# Sheet.net
KiCad netlist of a schematic drawn in Altium Designer
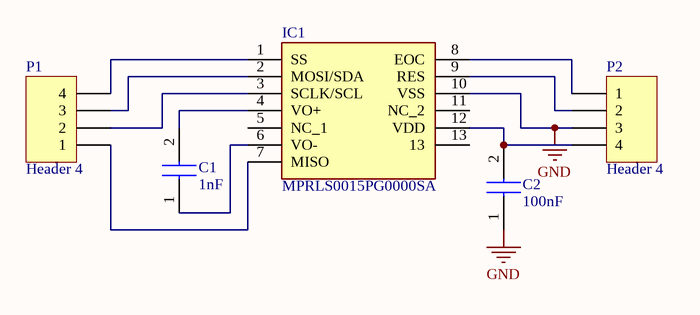
[diagram p0: Sheet.SchDoc]

(export (version "E")
  (design (tool "Eeschema 10.0.6"))
  (components
    (comp (ref "C1")
      (value "1nF")
      (footprint "SamacSys:CAPC2012X94N")
      (description "Capacitor")
      (fields
        (field (name "MANUFACTURER_PART_NUMBER") "08055A130JAT2A")
        (field (name "MOUSER PART NUMBER") "581-08055A130JAT2A")
      )
      (libsource (lib "SamacSys") (part "08055A130JAT2A"))
    )
    (comp (ref "C2")
      (value "100nF")
      (footprint "SamacSys:CAPC2012X94N")
      (description "Capacitor")
      (fields
        (field (name "MANUFACTURER_PART_NUMBER") "08055A130JAT2A")
        (field (name "MOUSER PART NUMBER") "581-08055A130JAT2A")
      )
      (libsource (lib "SamacSys") (part "08055A130JAT2A"))
    )
    (comp (ref "IC1")
      (value "MPRLS0015PG0000SA")
      (footprint "SamacSys:MPRLS0015PG0000SA")
      (description "Integrated Circuit")
      (libsource (lib "SamacSys") (part "MPRLS0015PG0000SA"))
    )
    (comp (ref "P1")
      (value "Header 4")
      (footprint "HDR1X4")
      (description "Header, 4-Pin")
      (fields (field (name "PUBLISHER") "Altium Limited"))
      (libsource (lib "") (part "Header 4_1"))
    )
    (comp (ref "P2")
      (value "Header 4")
      (footprint "HDR1X4")
      (description "Header, 4-Pin")
      (fields (field (name "PUBLISHER") "Altium Limited"))
      (libsource (lib "Miscellaneous Connectors") (part "Header 4"))
    )
  )
  (nets
    (net (code "1") (name "GND") (class "Default")
      (node (ref "C2") (pin "1") (pinfunction "1_1") (pintype "passive"))
      (node (ref "IC1") (pin "10") (pinfunction "VSS_10") (pintype "passive"))
      (node (ref "P2") (pin "3") (pinfunction "3_3") (pintype "passive"))
    )
    (net (code "2") (name "Net-(IC1-EOC)") (class "Default")
      (node (ref "IC1") (pin "8") (pinfunction "EOC_8") (pintype "passive"))
      (node (ref "P2") (pin "1") (pinfunction "1_1") (pintype "passive"))
    )
    (net (code "3") (name "Net-(IC1-MISO)") (class "Default")
      (node (ref "IC1") (pin "7") (pinfunction "MISO_7") (pintype "passive"))
      (node (ref "P1") (pin "1") (pinfunction "1_1") (pintype "passive"))
    )
    (net (code "4") (name "Net-(IC1-MOSI{slash}SDA)") (class "Default")
      (node (ref "IC1") (pin "2") (pinfunction "MOSI/SDA_2") (pintype "passive"))
      (node (ref "P1") (pin "3") (pinfunction "3_3") (pintype "passive"))
    )
    (net (code "5") (name "Net-(IC1-RES)") (class "Default")
      (node (ref "IC1") (pin "9") (pinfunction "RES_9") (pintype "passive"))
      (node (ref "P2") (pin "2") (pinfunction "2_2") (pintype "passive"))
    )
    (net (code "6") (name "Net-(IC1-SCLK{slash}SCL)") (class "Default")
      (node (ref "IC1") (pin "3") (pinfunction "SCLK/SCL_3") (pintype "passive"))
      (node (ref "P1") (pin "2") (pinfunction "2_2") (pintype "passive"))
    )
    (net (code "7") (name "Net-(IC1-SS)") (class "Default")
      (node (ref "IC1") (pin "1") (pinfunction "SS_1") (pintype "passive"))
      (node (ref "P1") (pin "4") (pinfunction "4_4") (pintype "passive"))
    )
    (net (code "8") (name "Net-(IC1-VDD)") (class "Default")
      (node (ref "C2") (pin "2") (pinfunction "2_2") (pintype "passive"))
      (node (ref "IC1") (pin "12") (pinfunction "VDD_12") (pintype "passive"))
      (node (ref "P2") (pin "4") (pinfunction "4_4") (pintype "passive"))
    )
    (net (code "9") (name "Net-(IC1-VO+)") (class "Default")
      (node (ref "C1") (pin "2") (pinfunction "2_2") (pintype "passive"))
      (node (ref "IC1") (pin "4") (pinfunction "VO+_4") (pintype "passive"))
    )
    (net (code "10") (name "Net-(IC1-VO-)") (class "Default")
      (node (ref "C1") (pin "1") (pinfunction "1_1") (pintype "passive"))
      (node (ref "IC1") (pin "6") (pinfunction "VO-_6") (pintype "passive"))
    )
    (net (code "11") (name "unconnected-(IC1-NC_1-Pad5)") (class "Default")
      (node (ref "IC1") (pin "5") (pinfunction "NC_1_5") (pintype "passive"))
    )
    (net (code "12") (name "unconnected-(IC1-NC_2-Pad11)") (class "Default")
      (node (ref "IC1") (pin "11") (pinfunction "NC_2_11") (pintype "passive"))
    )
    (net (code "13") (name "unconnected-(IC1-Pad13)") (class "Default")
      (node (ref "IC1") (pin "13") (pinfunction "13_13") (pintype "passive"))
    )
  )
)
